# 1_zasilanie.net
KiCad netlist of a schematic drawn in Altium Designer
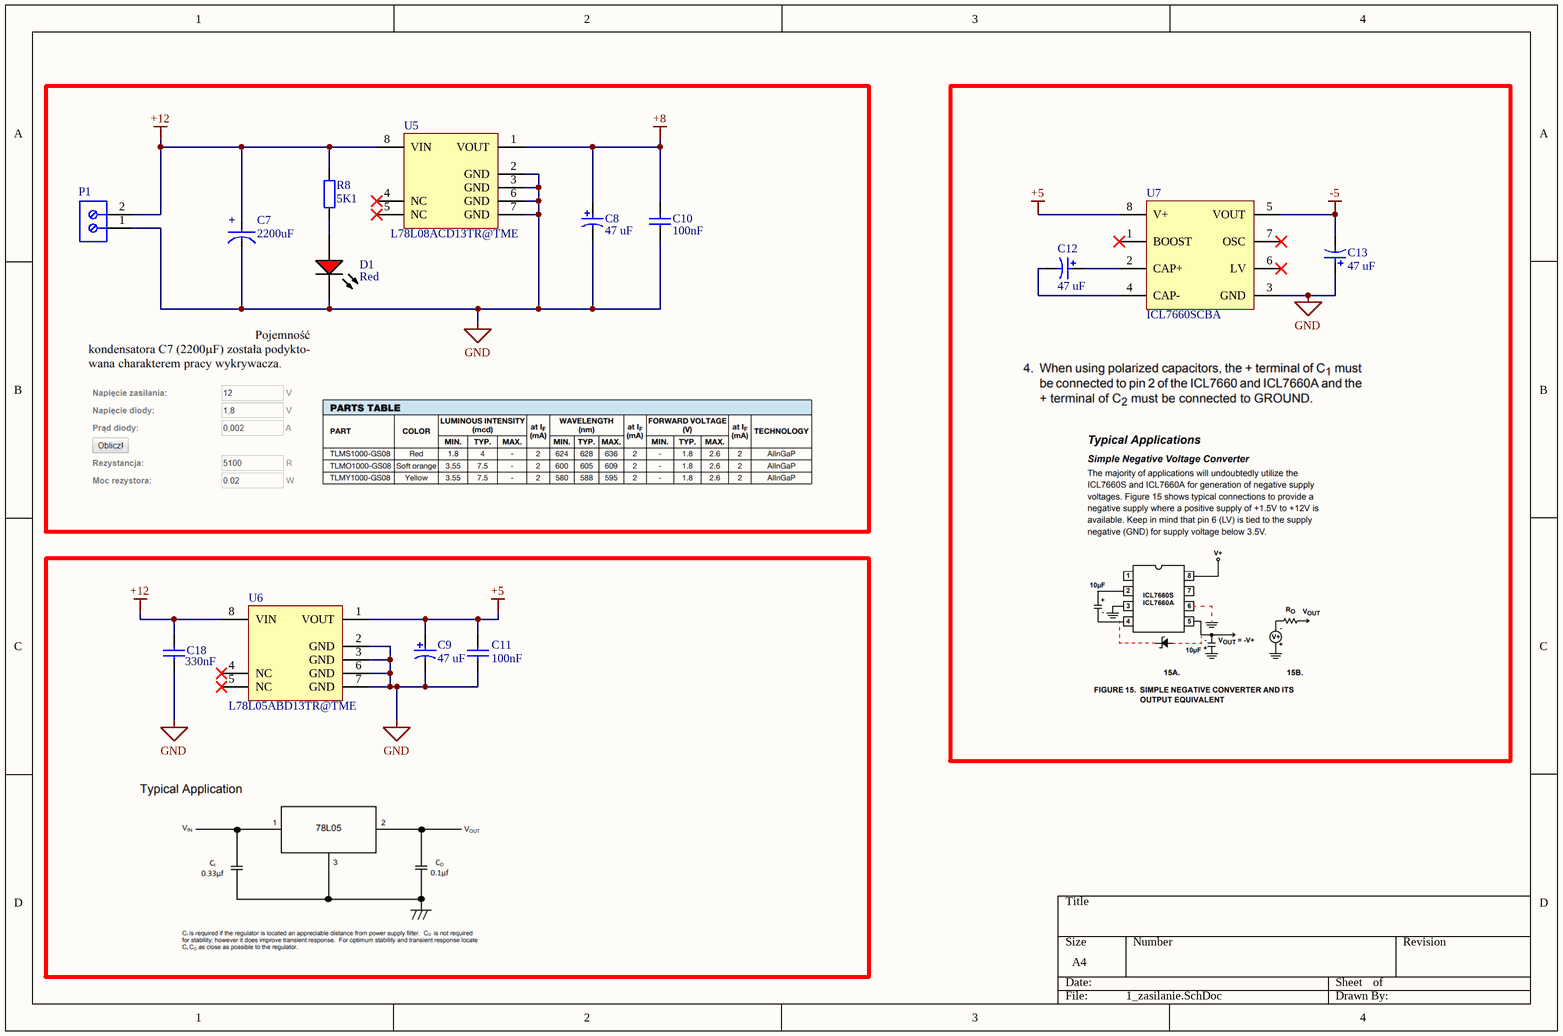
[diagram p0: 1_zasilanie.SchDoc]

(export (version "E")
  (design (tool "Eeschema 10.0.6"))
  (components
    (comp (ref "C7")
      (value "Cap Electrolytic")
      (footprint "Capacitors_MT_Library:18 X 25mm Radial 7.5mm")
      (description "CAPACITOR ALUM 2200UF 20% 35V RADIAL")
      (fields (field (name "CAPACITANCE") "2200uF"))
      (libsource (lib "MT_Library") (part "Cap Electrolytic"))
    )
    (comp (ref "C8")
      (value "UUD1E470MCL1GS")
      (footprint "NIC-CAPA2-6.3X5.8_V")
      (fields (field (name "MANUFACTURER") "Nichicon") (field (name "RATED CAPACITANCE") "47 uF"))
      (libsource (lib "Altium Content Vault") (part "NIC-CAP-P-2"))
    )
    (comp (ref "C9")
      (value "UUD1E470MCL1GS")
      (footprint "NIC-CAPA2-6.3X5.8_V")
      (fields (field (name "MANUFACTURER") "Nichicon") (field (name "RATED CAPACITANCE") "47 uF"))
      (libsource (lib "Altium Content Vault") (part "NIC-CAP-P-2"))
    )
    (comp (ref "C10")
      (value "CL10B104KA8NNNC@TME")
      (footprint "0603")
      (description "Capacitor")
      (fields (field (name "CAPACITANCE") "100nF"))
      (libsource (lib "MT_Library") (part "Cap"))
    )
    (comp (ref "C11")
      (value "CL10B104KA8NNNC@TME")
      (footprint "0603")
      (description "Capacitor")
      (fields (field (name "CAPACITANCE") "100nF"))
      (libsource (lib "MT_Library") (part "Cap"))
    )
    (comp (ref "C12")
      (value "UUD1E470MCL1GS")
      (footprint "NIC-CAPA2-6.3X5.8_V")
      (fields (field (name "MANUFACTURER") "Nichicon") (field (name "RATED CAPACITANCE") "47 uF"))
      (libsource (lib "Altium Content Vault") (part "NIC-CAP-P-2"))
    )
    (comp (ref "C13")
      (value "UUD1E470MCL1GS")
      (footprint "NIC-CAPA2-6.3X5.8_V")
      (fields (field (name "MANUFACTURER") "Nichicon") (field (name "RATED CAPACITANCE") "47 uF"))
      (libsource (lib "Altium Content Vault") (part "NIC-CAP-P-2"))
    )
    (comp (ref "C18")
      (value "330nF")
      (footprint "CAPC1608X90X35ML15T15")
      (fields
        (field (name "PART NUMBER") "0603YD334KAT2A")
        (field (name "MANUFACTURER") "AVX Interconnect / Elco")
      )
      (libsource (lib "Altium Content Vault") (part "CAP"))
    )
    (comp (ref "D1")
      (value "TLMS1000-GS08")
      (footprint "VISH-TLMS1000_V")
      (description "Low Current LED, 40 mW, 1.8 V, -40 to 100 degC, 2-Pin SMD (0603), RoHS, Tape and Reel")
      (fields (field (name "LED COLOUR") "Red") (field (name "MANUFACTURER") "Vishay"))
      (libsource (lib "Altium Content Vault") (part "LED-RED-AK-2"))
    )
    (comp (ref "P1")
      (value "282836-2@TME")
      (footprint "TECO-282836-2_V")
      (description "Female Header, Pitch 5 mm, 1 x 2 Position, Height 10 mm, Tail Length 3.5 mm, Rohs, Bulk")
      (fields (field (name "VOLTAGE") "300V") (field (name "MANUFACTURER") "TE Connectivity"))
      (libsource (lib "Altium Content Vault") (part "CN-1P-F-TB2"))
    )
    (comp (ref "R8")
      (value "5K1")
      (footprint "R1206")
      (description "Resistor")
      (fields (field (name "Comment") "1206S4J0102T5E@TME"))
      (libsource (lib "MT_Library") (part "Res"))
    )
    (comp (ref "U5")
      (value "L78L08ACD13TR@TME")
      (footprint "SO8_M")
      (description "Positive Voltage Regulator, 8V, 8-Pin SO, Tape and Reel")
      (libsource (lib "Altium Content Vault") (part "PM-REG-7805-IL8"))
    )
    (comp (ref "U6")
      (value "L78L05ABD13TR@TME")
      (footprint "SO8_N")
      (description "Positive Voltage Regulator, 5V, 8-Pin SO, Tape and Reel")
      (libsource (lib "Altium Content Vault") (part "PM-REG-7805-IL8"))
    )
    (comp (ref "U7")
      (value "ICL7660SCBA")
      (footprint "INTS-SOIC-8_V")
      (fields (field (name "MANUFACTURER") "Intersil"))
      (libsource (lib "Altium Content Vault") (part "INTS-ICL7660S-8"))
    )
  )
  (nets
    (net (code "1") (name "+5") (class "Default")
      (node (ref "C11") (pin "1") (pinfunction "1_1") (pintype "passive"))
      (node (ref "C9") (pin "1") (pinfunction "1_1") (pintype "passive"))
      (node (ref "U6") (pin "1") (pinfunction "VOUT_1") (pintype "power_in"))
      (node (ref "U7") (pin "8") (pinfunction "V+_8") (pintype "power_in"))
    )
    (net (code "2") (name "+8") (class "Default")
      (node (ref "C10") (pin "1") (pinfunction "1_1") (pintype "passive"))
      (node (ref "C8") (pin "1") (pinfunction "1_1") (pintype "passive"))
      (node (ref "U5") (pin "1") (pinfunction "VOUT_1") (pintype "power_in"))
    )
    (net (code "3") (name "+12") (class "Default")
      (node (ref "C18") (pin "1") (pinfunction "1_1") (pintype "passive"))
      (node (ref "C7") (pin "2") (pinfunction "+_2") (pintype "passive"))
      (node (ref "P1") (pin "2") (pinfunction "-_2") (pintype "power_in"))
      (node (ref "R8") (pin "2") (pinfunction "2_2") (pintype "passive"))
      (node (ref "U5") (pin "8") (pinfunction "VIN_8") (pintype "power_in"))
      (node (ref "U6") (pin "8") (pinfunction "VIN_8") (pintype "power_in"))
    )
    (net (code "4") (name "-5") (class "Default")
      (node (ref "C13") (pin "2") (pinfunction "2_2") (pintype "passive"))
      (node (ref "U7") (pin "5") (pinfunction "VOUT_5") (pintype "power_in"))
    )
    (net (code "5") (name "GND") (class "Default")
      (node (ref "C10") (pin "2") (pinfunction "2_2") (pintype "passive"))
      (node (ref "C11") (pin "2") (pinfunction "2_2") (pintype "passive"))
      (node (ref "C13") (pin "1") (pinfunction "1_1") (pintype "passive"))
      (node (ref "C18") (pin "2") (pinfunction "2_2") (pintype "passive"))
      (node (ref "C7") (pin "1") (pinfunction "-_1") (pintype "passive"))
      (node (ref "C8") (pin "2") (pinfunction "2_2") (pintype "passive"))
      (node (ref "C9") (pin "2") (pinfunction "2_2") (pintype "passive"))
      (node (ref "D1") (pin "2") (pinfunction "K_2") (pintype "passive"))
      (node (ref "P1") (pin "1") (pinfunction "+_1") (pintype "power_in"))
      (node (ref "U5") (pin "2") (pinfunction "GND_2") (pintype "power_in"))
      (node (ref "U5") (pin "3") (pinfunction "GND_3") (pintype "power_in"))
      (node (ref "U5") (pin "6") (pinfunction "GND_6") (pintype "power_in"))
      (node (ref "U5") (pin "7") (pinfunction "GND_7") (pintype "power_in"))
      (node (ref "U6") (pin "2") (pinfunction "GND_2") (pintype "power_in"))
      (node (ref "U6") (pin "3") (pinfunction "GND_3") (pintype "power_in"))
      (node (ref "U6") (pin "6") (pinfunction "GND_6") (pintype "power_in"))
      (node (ref "U6") (pin "7") (pinfunction "GND_7") (pintype "power_in"))
      (node (ref "U7") (pin "3") (pinfunction "GND_3") (pintype "power_in"))
    )
    (net (code "6") (name "Net-(D1-A)") (class "Default")
      (node (ref "D1") (pin "1") (pinfunction "A_1") (pintype "passive"))
      (node (ref "R8") (pin "1") (pinfunction "1_1") (pintype "passive"))
    )
    (net (code "7") (name "Net-(U7-CAP+)") (class "Default")
      (node (ref "C12") (pin "1") (pinfunction "1_1") (pintype "passive"))
      (node (ref "U7") (pin "2") (pinfunction "CAP+_2") (pintype "passive"))
    )
    (net (code "8") (name "Net-(U7-CAP-)") (class "Default")
      (node (ref "C12") (pin "2") (pinfunction "2_2") (pintype "passive"))
      (node (ref "U7") (pin "4") (pinfunction "CAP-_4") (pintype "passive"))
    )
    (net (code "9") (name "unconnected-(U5-NC-Pad4)") (class "Default")
      (node (ref "U5") (pin "4") (pinfunction "NC_4") (pintype "passive+no_connect"))
    )
    (net (code "10") (name "unconnected-(U5-NC-Pad5)") (class "Default")
      (node (ref "U5") (pin "5") (pinfunction "NC_5") (pintype "passive+no_connect"))
    )
    (net (code "11") (name "unconnected-(U6-NC-Pad4)") (class "Default")
      (node (ref "U6") (pin "4") (pinfunction "NC_4") (pintype "passive+no_connect"))
    )
    (net (code "12") (name "unconnected-(U6-NC-Pad5)") (class "Default")
      (node (ref "U6") (pin "5") (pinfunction "NC_5") (pintype "passive+no_connect"))
    )
    (net (code "13") (name "unconnected-(U7-BOOST-Pad1)") (class "Default")
      (node (ref "U7") (pin "1") (pinfunction "BOOST_1") (pintype "passive+no_connect"))
    )
    (net (code "14") (name "unconnected-(U7-LV-Pad6)") (class "Default")
      (node (ref "U7") (pin "6") (pinfunction "LV_6") (pintype "power_in+no_connect"))
    )
    (net (code "15") (name "unconnected-(U7-OSC-Pad7)") (class "Default")
      (node (ref "U7") (pin "7") (pinfunction "OSC_7") (pintype "passive+no_connect"))
    )
  )
)
